# Partical_Sensor.net
KiCad netlist of a schematic drawn in Altium Designer
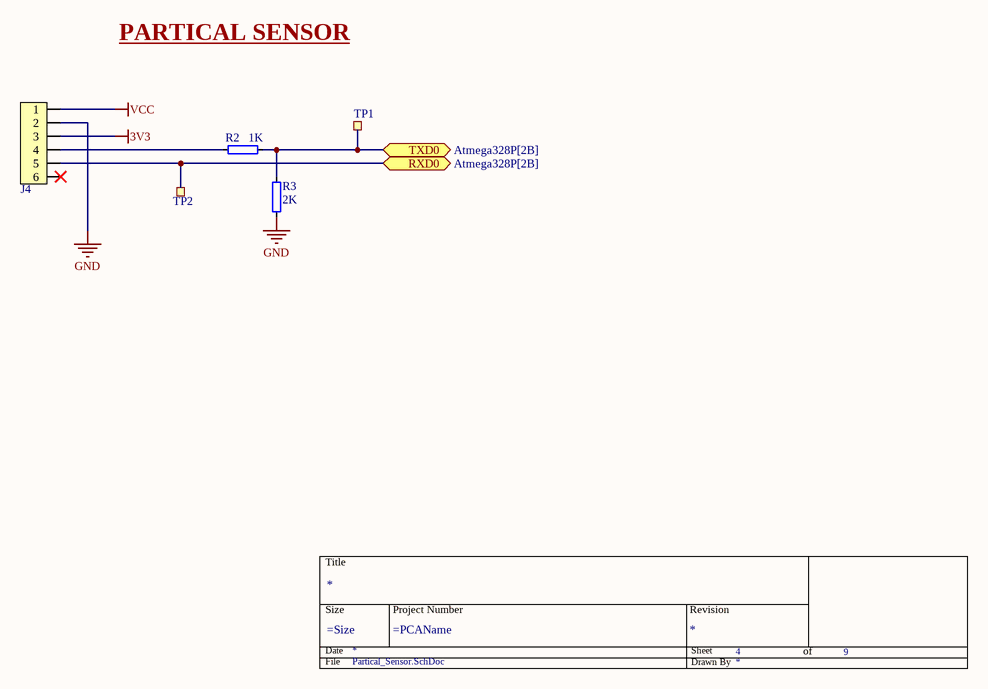
[diagram p0: Partical_Sensor.SchDoc]

(export (version "E")
  (design (tool "Eeschema 10.0.6"))
  (components
    (comp (ref "*") (value "Title Block") (libsource (lib "HEPA_LIB") (part "Title Block")))
    (comp (ref "J4")
      (value "6way Connector")
      (footprint "TE_640455-6")
      (description "6Way Right Angle JST-XH connector Male 2.54mm Pitch")
      (fields (field (name "PART NUMBER") "JST-XH") (field (name "PUBLISHER") "Metal Circuits"))
      (libsource (lib "HEPA_LIB") (part "JST 6Way Connector RA"))
    )
    (comp (ref "R2")
      (value "1K")
      (footprint "RESC2012X65N")
      (description "RES SMD 1% 1/10W 0805")
      (fields (field (name "PART NUMBER") "RES_0805") (field (name "PUBLISHER") "Metal Circuits"))
      (libsource (lib "HEPA_LIB") (part "RES_0805"))
    )
    (comp (ref "R3")
      (value "2K")
      (footprint "RESC2012X65N")
      (description "RES SMD 1% 1/10W 0805")
      (fields (field (name "PART NUMBER") "RES_0805") (field (name "PUBLISHER") "Metal Circuits"))
      (libsource (lib "HEPA_LIB") (part "RES_0805"))
    )
    (comp (ref "TP1")
      (value "TP")
      (footprint "TESTPAD-TH")
      (description "Testpoint, through hole")
      (fields (field (name "PART NUMBER") "Testpoint TH") (field (name "PUBLISHER") "Nordic Semiconductor"))
      (libsource (lib "HEPA_LIB") (part "TESTPAD_TH"))
    )
    (comp (ref "TP2")
      (value "TP")
      (footprint "TESTPAD-TH")
      (description "Testpoint, through hole")
      (fields (field (name "PART NUMBER") "Testpoint TH") (field (name "PUBLISHER") "Nordic Semiconductor"))
      (libsource (lib "") (part "TESTPAD_TH_1"))
    )
  )
  (nets
    (net (code "1") (name "/RXD0") (class "Default")
      (node (ref "J4") (pin "5") (pinfunction "5_5") (pintype "passive"))
      (node (ref "TP2") (pin "1") (pinfunction "1_1") (pintype "passive"))
    )
    (net (code "2") (name "/TXD0") (class "Default")
      (node (ref "R2") (pin "1") (pinfunction "1_1") (pintype "passive"))
      (node (ref "R3") (pin "2") (pinfunction "2_2") (pintype "passive"))
      (node (ref "TP1") (pin "1") (pinfunction "1_1") (pintype "passive"))
    )
    (net (code "3") (name "3V3") (class "Default")
      (node (ref "J4") (pin "3") (pinfunction "3_3") (pintype "passive"))
    )
    (net (code "4") (name "GND") (class "Default")
      (node (ref "J4") (pin "2") (pinfunction "2_2") (pintype "passive"))
      (node (ref "R3") (pin "1") (pinfunction "1_1") (pintype "passive"))
    )
    (net (code "5") (name "Net-(J4-Pad4)") (class "Default")
      (node (ref "J4") (pin "4") (pinfunction "4_4") (pintype "passive"))
      (node (ref "R2") (pin "2") (pinfunction "2_2") (pintype "passive"))
    )
    (net (code "6") (name "VCC") (class "Default")
      (node (ref "J4") (pin "1") (pinfunction "1_1") (pintype "passive"))
    )
    (net (code "7") (name "unconnected-(J4-Pad6)") (class "Default")
      (node (ref "J4") (pin "6") (pinfunction "6_6") (pintype "passive+no_connect"))
    )
  )
)
